# stepper.net
KiCad netlist of a schematic drawn in EAGLE
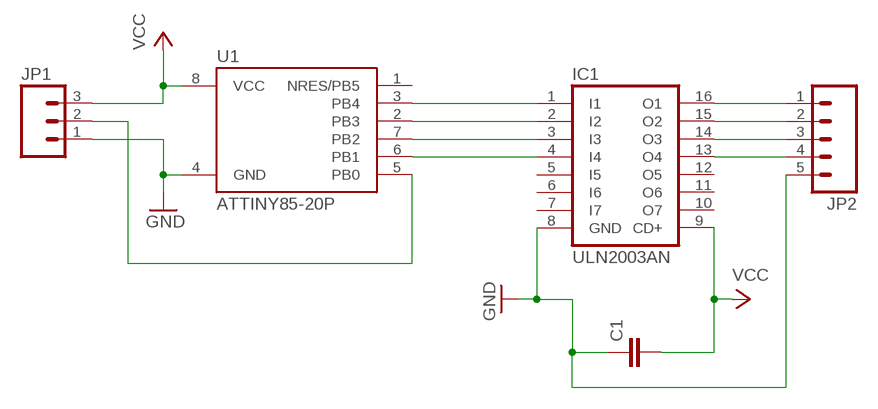
[diagram p0: schematic, sheet 1]

(export (version "E")
  (design (tool "Eeschema 10.0.6"))
  (components
    (comp (ref "C1")
      (value "C-EU025-025X050")
      (footprint "eagle-import:C025-025X050")
      (libsource (lib "eagle-import") (part "C-EU025-025X050"))
    )
    (comp (ref "IC1")
      (value "ULN2003AN")
      (footprint "eagle-import:DIL16")
      (libsource (lib "eagle-import") (part "ULN2003AN"))
    )
    (comp (ref "JP1")
      (value "M03JST-PTH")
      (footprint "eagle-import:JST-3-PTH")
      (libsource (lib "eagle-import") (part "M03JST-PTH"))
    )
    (comp (ref "JP2")
      (value "M05PTH_LONGPADS")
      (footprint "eagle-import:1X05_LONGPADS")
      (libsource (lib "eagle-import") (part "M05PTH_LONGPADS"))
    )
    (comp (ref "U1")
      (value "ATTINY85-20P")
      (footprint "eagle-import:PDIP08_300MIL")
      (libsource (lib "eagle-import") (part "ATTINY85P-20"))
    )
  )
  (nets
    (net (code "1") (name "GND") (class "Default")
      (node (ref "C1") (pin "1") (pinfunction "1_1") (pintype "passive"))
      (node (ref "IC1") (pin "8") (pinfunction "GND_8") (pintype "power_in"))
      (node (ref "JP1") (pin "1") (pinfunction "1_1") (pintype "passive"))
      (node (ref "JP2") (pin "5") (pinfunction "5_5") (pintype "passive"))
      (node (ref "U1") (pin "4") (pinfunction "GND_4") (pintype "power_in"))
    )
    (net (code "2") (name "Net-(IC1-I1)") (class "Default")
      (node (ref "IC1") (pin "1") (pinfunction "I1_1") (pintype "input"))
      (node (ref "U1") (pin "3") (pinfunction "PB4_3") (pintype "bidirectional"))
    )
    (net (code "3") (name "Net-(IC1-I2)") (class "Default")
      (node (ref "IC1") (pin "2") (pinfunction "I2_2") (pintype "input"))
      (node (ref "U1") (pin "2") (pinfunction "PB3_2") (pintype "bidirectional"))
    )
    (net (code "4") (name "Net-(IC1-I3)") (class "Default")
      (node (ref "IC1") (pin "3") (pinfunction "I3_3") (pintype "input"))
      (node (ref "U1") (pin "7") (pinfunction "PB2_7") (pintype "bidirectional"))
    )
    (net (code "5") (name "Net-(IC1-I4)") (class "Default")
      (node (ref "IC1") (pin "4") (pinfunction "I4_4") (pintype "input"))
      (node (ref "U1") (pin "6") (pinfunction "PB1_6") (pintype "bidirectional"))
    )
    (net (code "6") (name "Net-(IC1-O1)") (class "Default")
      (node (ref "IC1") (pin "16") (pinfunction "O1_16") (pintype "open_collector"))
      (node (ref "JP2") (pin "1") (pinfunction "1_1") (pintype "passive"))
    )
    (net (code "7") (name "Net-(IC1-O2)") (class "Default")
      (node (ref "IC1") (pin "15") (pinfunction "O2_15") (pintype "open_collector"))
      (node (ref "JP2") (pin "2") (pinfunction "2_2") (pintype "passive"))
    )
    (net (code "8") (name "Net-(IC1-O3)") (class "Default")
      (node (ref "IC1") (pin "14") (pinfunction "O3_14") (pintype "open_collector"))
      (node (ref "JP2") (pin "3") (pinfunction "3_3") (pintype "passive"))
    )
    (net (code "9") (name "Net-(IC1-O4)") (class "Default")
      (node (ref "IC1") (pin "13") (pinfunction "O4_13") (pintype "open_collector"))
      (node (ref "JP2") (pin "4") (pinfunction "4_4") (pintype "passive"))
    )
    (net (code "10") (name "Net-(U1-PB0)") (class "Default")
      (node (ref "JP1") (pin "2") (pinfunction "2_2") (pintype "passive"))
      (node (ref "U1") (pin "5") (pinfunction "PB0_5") (pintype "bidirectional"))
    )
    (net (code "11") (name "VCC") (class "Default")
      (node (ref "C1") (pin "2") (pinfunction "2_2") (pintype "passive"))
      (node (ref "IC1") (pin "9") (pinfunction "CD+_9") (pintype "passive"))
      (node (ref "JP1") (pin "3") (pinfunction "3_3") (pintype "passive"))
      (node (ref "U1") (pin "8") (pinfunction "VCC_8") (pintype "power_in"))
    )
    (net (code "12") (name "unconnected-(IC1-I5-Pad5)") (class "Default")
      (node (ref "IC1") (pin "5") (pinfunction "I5_5") (pintype "input"))
    )
    (net (code "13") (name "unconnected-(IC1-I6-Pad6)") (class "Default")
      (node (ref "IC1") (pin "6") (pinfunction "I6_6") (pintype "input"))
    )
    (net (code "14") (name "unconnected-(IC1-I7-Pad7)") (class "Default")
      (node (ref "IC1") (pin "7") (pinfunction "I7_7") (pintype "input"))
    )
    (net (code "15") (name "unconnected-(IC1-O5-Pad12)") (class "Default")
      (node (ref "IC1") (pin "12") (pinfunction "O5_12") (pintype "open_collector"))
    )
    (net (code "16") (name "unconnected-(IC1-O6-Pad11)") (class "Default")
      (node (ref "IC1") (pin "11") (pinfunction "O6_11") (pintype "open_collector"))
    )
    (net (code "17") (name "unconnected-(IC1-O7-Pad10)") (class "Default")
      (node (ref "IC1") (pin "10") (pinfunction "O7_10") (pintype "open_collector"))
    )
    (net (code "18") (name "unconnected-(U1-NRES{slash}PB5-Pad1)") (class "Default")
      (node (ref "U1") (pin "1") (pinfunction "NRES/PB5_1") (pintype "bidirectional"))
    )
  )
)
